# Modbus.net
KiCad netlist of a schematic drawn in Altium Designer
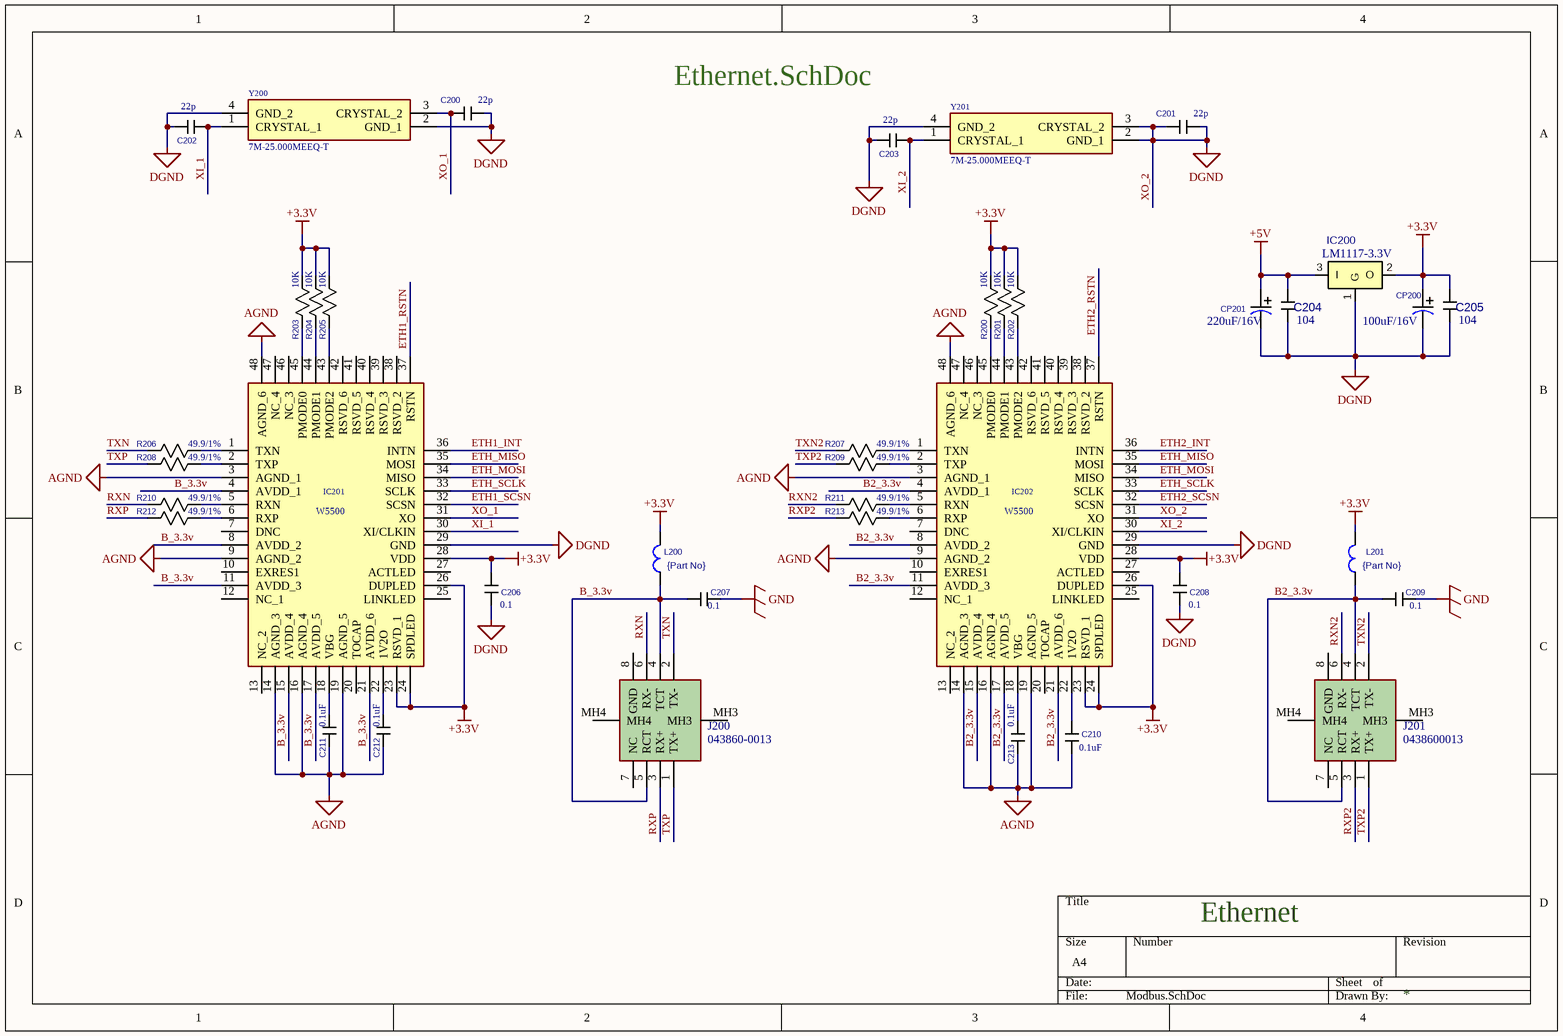
[diagram p0: Modbus.SchDoc]

(export (version "E")
  (design (tool "Eeschema 10.0.6"))
  (components
    (comp (ref "C200")
      (value "CS1608")
      (footprint "CC1608")
      (fields (field (name "PART NO.") "{Part No}") (field (name "규격") "22p"))
      (libsource (lib "KipoAlt") (part "CS1608"))
    )
    (comp (ref "C201")
      (value "CS1608")
      (footprint "CC1608")
      (fields (field (name "PART NO.") "{Part No}") (field (name "규격") "22p"))
      (libsource (lib "KipoAlt") (part "CS1608"))
    )
    (comp (ref "C202")
      (value "CS1608")
      (footprint "CC1608")
      (fields (field (name "PART NO.") "{Part No}") (field (name "규격") "22p"))
      (libsource (lib "KipoAlt") (part "CS1608"))
    )
    (comp (ref "C203")
      (value "CS1608")
      (footprint "CC1608")
      (fields (field (name "PART NO.") "{Part No}") (field (name "규격") "22p"))
      (libsource (lib "KipoAlt") (part "CS1608"))
    )
    (comp (ref "C204")
      (value "CS1608")
      (footprint "CC1608")
      (fields (field (name "PART NO.") "{Part No}") (field (name "규격") "104"))
      (libsource (lib "KipoAlt") (part "CS1608"))
    )
    (comp (ref "C205")
      (value "CS1608")
      (footprint "CC1608")
      (fields (field (name "PART NO.") "{Part No}") (field (name "규격") "104"))
      (libsource (lib "KipoAlt") (part "CS1608"))
    )
    (comp (ref "C206")
      (value "CS1608")
      (footprint "CC1608")
      (fields (field (name "PART NO.") "{Part No}") (field (name "규격") "0.1"))
      (libsource (lib "KipoAlt") (part "CS1608"))
    )
    (comp (ref "C207")
      (value "CS1608")
      (footprint "CC1608")
      (fields (field (name "PART NO.") "{Part No}") (field (name "규격") "0.1"))
      (libsource (lib "KipoAlt") (part "CS1608"))
    )
    (comp (ref "C208")
      (value "CS1608")
      (footprint "CC1608")
      (fields (field (name "PART NO.") "{Part No}") (field (name "규격") "0.1"))
      (libsource (lib "KipoAlt") (part "CS1608"))
    )
    (comp (ref "C209")
      (value "CS1608")
      (footprint "CC1608")
      (fields (field (name "PART NO.") "{Part No}") (field (name "규격") "0.1"))
      (libsource (lib "KipoAlt") (part "CS1608"))
    )
    (comp (ref "C210")
      (value "CS1608")
      (footprint "CC1608")
      (fields (field (name "PART NO.") "{Part No}") (field (name "규격") "0.1uF"))
      (libsource (lib "KipoAlt") (part "CS1608"))
    )
    (comp (ref "C211")
      (value "CS1608")
      (footprint "CC1608")
      (fields (field (name "PART NO.") "{Part No}") (field (name "규격") "0.1uF"))
      (libsource (lib "KipoAlt") (part "CS1608"))
    )
    (comp (ref "C212")
      (value "CS1608")
      (footprint "CC1608")
      (fields (field (name "PART NO.") "{Part No}") (field (name "규격") "0.1uF"))
      (libsource (lib "KipoAlt") (part "CS1608"))
    )
    (comp (ref "C213")
      (value "CS1608")
      (footprint "CC1608")
      (fields (field (name "PART NO.") "{Part No}") (field (name "규격") "0.1uF"))
      (libsource (lib "KipoAlt") (part "CS1608"))
    )
    (comp (ref "CP200")
      (value "CP5_SMT")
      (footprint "CP5_SMT")
      (fields (field (name "규격") "100uF/16V") (field (name "PART NO.") "{Part No}"))
      (libsource (lib "KipoAlt") (part "CP5_SMT"))
    )
    (comp (ref "CP201")
      (value "CP6_SMT")
      (footprint "CP6_SMT")
      (fields (field (name "PART NO.") "RV16V220 6.3X7.7 (ELNA / 삼영)") (field (name "규격") "220uF/16V"))
      (libsource (lib "KipoAlt") (part "CP6_SMT"))
    )
    (comp (ref "IC200")
      (value "1117SO")
      (footprint "SOT-223")
      (fields (field (name "PART NO.") "LM1117-3.3V"))
      (libsource (lib "KipoAlt") (part "1117SO"))
    )
    (comp (ref "IC201")
      (value "W5500")
      (footprint "KipoAlt:QFP50P900X900X160-48N")
      (description "Integrated Circuit")
      (libsource (lib "*") (part "W5500"))
    )
    (comp (ref "IC202")
      (value "W5500")
      (footprint "KipoAlt:QFP50P900X900X160-48N")
      (description "Integrated Circuit")
      (libsource (lib "*") (part "W5500"))
    )
    (comp (ref "J200")
      (value "043860-0013")
      (footprint "KipoAlt:0438600013")
      (description "Connector")
      (fields (field (name "MANUFACTURER_PART_NUMBER") "0438600013"))
      (libsource (lib "KipoAlt") (part "0438600013"))
    )
    (comp (ref "J201")
      (value "0438600013")
      (footprint "KipoAlt:0438600013")
      (description "Connector")
      (libsource (lib "KipoAlt") (part "0438600013"))
    )
    (comp (ref "L200")
      (value "L")
      (footprint "BEADC2012X110N")
      (fields (field (name "PART NO.") "{Part No}"))
      (libsource (lib "KipoAlt") (part "BEAD2012"))
    )
    (comp (ref "L201")
      (value "L")
      (footprint "BEADC2012X110N")
      (fields (field (name "PART NO.") "{Part No}"))
      (libsource (lib "KipoAlt") (part "BEAD2012"))
    )
    (comp (ref "R200")
      (value "R1608")
      (footprint "R1608N")
      (fields (field (name "규격") "10K") (field (name "PART NO.") "{Part No}"))
      (libsource (lib "KipoAlt") (part "R1608"))
    )
    (comp (ref "R201")
      (value "R1608")
      (footprint "R1608N")
      (fields (field (name "규격") "10K") (field (name "PART NO.") "{Part No}"))
      (libsource (lib "KipoAlt") (part "R1608"))
    )
    (comp (ref "R202")
      (value "R1608")
      (footprint "R1608N")
      (fields (field (name "규격") "10K") (field (name "PART NO.") "{Part No}"))
      (libsource (lib "KipoAlt") (part "R1608"))
    )
    (comp (ref "R203")
      (value "R1608")
      (footprint "R1608N")
      (fields (field (name "규격") "10K") (field (name "PART NO.") "{Part No}"))
      (libsource (lib "KipoAlt") (part "R1608"))
    )
    (comp (ref "R204")
      (value "R1608")
      (footprint "R1608N")
      (fields (field (name "규격") "10K") (field (name "PART NO.") "{Part No}"))
      (libsource (lib "KipoAlt") (part "R1608"))
    )
    (comp (ref "R205")
      (value "R1608")
      (footprint "R1608N")
      (fields (field (name "규격") "10K") (field (name "PART NO.") "{Part No}"))
      (libsource (lib "KipoAlt") (part "R1608"))
    )
    (comp (ref "R206")
      (value "R1608")
      (footprint "R1608N")
      (fields (field (name "규격") "49.9/1%") (field (name "PART NO.") "{Part No}"))
      (libsource (lib "KipoAlt") (part "R1608"))
    )
    (comp (ref "R207")
      (value "R1608")
      (footprint "R1608N")
      (fields (field (name "규격") "49.9/1%") (field (name "PART NO.") "{Part No}"))
      (libsource (lib "KipoAlt") (part "R1608"))
    )
    (comp (ref "R208")
      (value "R1608")
      (footprint "R1608N")
      (fields (field (name "규격") "49.9/1%") (field (name "PART NO.") "{Part No}"))
      (libsource (lib "KipoAlt") (part "R1608"))
    )
    (comp (ref "R209")
      (value "R1608")
      (footprint "R1608N")
      (fields (field (name "규격") "49.9/1%") (field (name "PART NO.") "{Part No}"))
      (libsource (lib "KipoAlt") (part "R1608"))
    )
    (comp (ref "R210")
      (value "R1608")
      (footprint "R1608N")
      (fields (field (name "규격") "49.9/1%") (field (name "PART NO.") "{Part No}"))
      (libsource (lib "KipoAlt") (part "R1608"))
    )
    (comp (ref "R211")
      (value "R1608")
      (footprint "R1608N")
      (fields (field (name "규격") "49.9/1%") (field (name "PART NO.") "{Part No}"))
      (libsource (lib "KipoAlt") (part "R1608"))
    )
    (comp (ref "R212")
      (value "R1608")
      (footprint "R1608N")
      (fields (field (name "규격") "49.9/1%") (field (name "PART NO.") "{Part No}"))
      (libsource (lib "KipoAlt") (part "R1608"))
    )
    (comp (ref "R213")
      (value "R1608")
      (footprint "R1608N")
      (fields (field (name "규격") "49.9/1%") (field (name "PART NO.") "{Part No}"))
      (libsource (lib "KipoAlt") (part "R1608"))
    )
    (comp (ref "Y200")
      (value "7M-25.000MEEQ-T")
      (footprint "KipoAlt:7M25000MEEQT")
      (description "Crystal or Oscillator")
      (fields (field (name "MOUSER PART NUMBER") "717-7M-25.000MEEQ-T"))
      (libsource (lib "*") (part "7M-25.000MEEQ-T"))
    )
    (comp (ref "Y201")
      (value "7M-25.000MEEQ-T")
      (footprint "KipoAlt:7M25000MEEQT")
      (description "Crystal or Oscillator")
      (fields (field (name "MOUSER PART NUMBER") "717-7M-25.000MEEQ-T"))
      (libsource (lib "*") (part "7M-25.000MEEQ-T"))
    )
  )
  (nets
    (net (code "1") (name "+3.3V") (class "Default")
      (node (ref "C205") (pin "2") (pintype "passive"))
      (node (ref "C206") (pin "2") (pintype "passive"))
      (node (ref "C208") (pin "2") (pintype "passive"))
      (node (ref "CP200") (pin "2") (pintype "passive"))
      (node (ref "IC200") (pin "2") (pinfunction "O_2") (pintype "passive"))
      (node (ref "IC201") (pin "23") (pinfunction "RSVD_1_23") (pintype "passive"))
      (node (ref "IC201") (pin "24") (pinfunction "SPDLED_24") (pintype "passive"))
      (node (ref "IC201") (pin "26") (pinfunction "DUPLED_26") (pintype "passive"))
      (node (ref "IC201") (pin "28") (pinfunction "VDD_28") (pintype "passive"))
      (node (ref "IC202") (pin "23") (pinfunction "RSVD_1_23") (pintype "passive"))
      (node (ref "IC202") (pin "24") (pinfunction "SPDLED_24") (pintype "passive"))
      (node (ref "IC202") (pin "26") (pinfunction "DUPLED_26") (pintype "passive"))
      (node (ref "IC202") (pin "28") (pinfunction "VDD_28") (pintype "passive"))
      (node (ref "L200") (pin "1") (pintype "passive"))
      (node (ref "L201") (pin "1") (pintype "passive"))
      (node (ref "R200") (pin "1") (pintype "passive"))
      (node (ref "R201") (pin "1") (pintype "passive"))
      (node (ref "R202") (pin "1") (pintype "passive"))
      (node (ref "R203") (pin "1") (pintype "passive"))
      (node (ref "R204") (pin "1") (pintype "passive"))
      (node (ref "R205") (pin "1") (pintype "passive"))
    )
    (net (code "2") (name "+5V") (class "Default")
      (node (ref "C204") (pin "2") (pintype "passive"))
      (node (ref "CP201") (pin "2") (pintype "passive"))
      (node (ref "IC200") (pin "3") (pinfunction "I_3") (pintype "passive"))
    )
    (net (code "3") (name "/B2_3.3v") (class "Default")
      (node (ref "C209") (pin "2") (pintype "passive"))
      (node (ref "IC202") (pin "11") (pinfunction "AVDD_3_11") (pintype "passive"))
      (node (ref "IC202") (pin "15") (pinfunction "AVDD_4_15") (pintype "passive"))
      (node (ref "IC202") (pin "17") (pinfunction "AVDD_5_17") (pintype "passive"))
      (node (ref "IC202") (pin "21") (pinfunction "AVDD_6_21") (pintype "passive"))
      (node (ref "IC202") (pin "4") (pinfunction "AVDD_1_4") (pintype "passive"))
      (node (ref "IC202") (pin "8") (pinfunction "AVDD_2_8") (pintype "passive"))
      (node (ref "J201") (pin "4") (pinfunction "TCT_4") (pintype "passive"))
      (node (ref "J201") (pin "5") (pinfunction "RCT_5") (pintype "passive"))
      (node (ref "L201") (pin "2") (pintype "passive"))
    )
    (net (code "4") (name "/B_3.3v") (class "Default")
      (node (ref "C207") (pin "2") (pintype "passive"))
      (node (ref "IC201") (pin "11") (pinfunction "AVDD_3_11") (pintype "passive"))
      (node (ref "IC201") (pin "15") (pinfunction "AVDD_4_15") (pintype "passive"))
      (node (ref "IC201") (pin "17") (pinfunction "AVDD_5_17") (pintype "passive"))
      (node (ref "IC201") (pin "21") (pinfunction "AVDD_6_21") (pintype "passive"))
      (node (ref "IC201") (pin "4") (pinfunction "AVDD_1_4") (pintype "passive"))
      (node (ref "IC201") (pin "8") (pinfunction "AVDD_2_8") (pintype "passive"))
      (node (ref "J200") (pin "4") (pinfunction "TCT_4") (pintype "passive"))
      (node (ref "J200") (pin "5") (pinfunction "RCT_5") (pintype "passive"))
      (node (ref "L200") (pin "2") (pintype "passive"))
    )
    (net (code "5") (name "/ETH1_INT") (class "Default")
      (node (ref "IC201") (pin "36") (pinfunction "INTN_36") (pintype "passive"))
    )
    (net (code "6") (name "/ETH1_RSTN") (class "Default")
      (node (ref "IC201") (pin "37") (pinfunction "RSTN_37") (pintype "passive"))
    )
    (net (code "7") (name "/ETH1_SCSN") (class "Default")
      (node (ref "IC201") (pin "32") (pinfunction "SCSN_32") (pintype "passive"))
    )
    (net (code "8") (name "/ETH2_INT") (class "Default")
      (node (ref "IC202") (pin "36") (pinfunction "INTN_36") (pintype "passive"))
    )
    (net (code "9") (name "/ETH2_RSTN") (class "Default")
      (node (ref "IC202") (pin "37") (pinfunction "RSTN_37") (pintype "passive"))
    )
    (net (code "10") (name "/ETH2_SCSN") (class "Default")
      (node (ref "IC202") (pin "32") (pinfunction "SCSN_32") (pintype "passive"))
    )
    (net (code "11") (name "/ETH_MISO") (class "Default")
      (node (ref "IC201") (pin "35") (pinfunction "MOSI_35") (pintype "passive"))
      (node (ref "IC202") (pin "35") (pinfunction "MOSI_35") (pintype "passive"))
    )
    (net (code "12") (name "/ETH_MOSI") (class "Default")
      (node (ref "IC201") (pin "34") (pinfunction "MISO_34") (pintype "passive"))
      (node (ref "IC202") (pin "34") (pinfunction "MISO_34") (pintype "passive"))
    )
    (net (code "13") (name "/ETH_SCLK") (class "Default")
      (node (ref "IC201") (pin "33") (pinfunction "SCLK_33") (pintype "passive"))
      (node (ref "IC202") (pin "33") (pinfunction "SCLK_33") (pintype "passive"))
    )
    (net (code "14") (name "/RXN") (class "Default")
      (node (ref "J200") (pin "6") (pinfunction "RX-_6") (pintype "passive"))
      (node (ref "R210") (pin "1") (pintype "passive"))
    )
    (net (code "15") (name "/RXN2") (class "Default")
      (node (ref "J201") (pin "6") (pinfunction "RX-_6") (pintype "passive"))
      (node (ref "R211") (pin "1") (pintype "passive"))
    )
    (net (code "16") (name "/RXP") (class "Default")
      (node (ref "J200") (pin "3") (pinfunction "RX+_3") (pintype "passive"))
      (node (ref "R212") (pin "1") (pintype "passive"))
    )
    (net (code "17") (name "/RXP2") (class "Default")
      (node (ref "J201") (pin "3") (pinfunction "RX+_3") (pintype "passive"))
      (node (ref "R213") (pin "1") (pintype "passive"))
    )
    (net (code "18") (name "/TXN") (class "Default")
      (node (ref "J200") (pin "2") (pinfunction "TX-_2") (pintype "passive"))
      (node (ref "R206") (pin "1") (pintype "passive"))
    )
    (net (code "19") (name "/TXN2") (class "Default")
      (node (ref "J201") (pin "2") (pinfunction "TX-_2") (pintype "passive"))
      (node (ref "R207") (pin "1") (pintype "passive"))
    )
    (net (code "20") (name "/TXP") (class "Default")
      (node (ref "J200") (pin "1") (pinfunction "TX+_1") (pintype "passive"))
      (node (ref "R208") (pin "1") (pintype "passive"))
    )
    (net (code "21") (name "/TXP2") (class "Default")
      (node (ref "J201") (pin "1") (pinfunction "TX+_1") (pintype "passive"))
      (node (ref "R209") (pin "1") (pintype "passive"))
    )
    (net (code "22") (name "/XI_1") (class "Default")
      (node (ref "C202") (pin "1") (pintype "passive"))
      (node (ref "IC201") (pin "30") (pinfunction "XI/CLKIN_30") (pintype "passive"))
      (node (ref "Y200") (pin "1") (pinfunction "CRYSTAL_1_1") (pintype "passive"))
    )
    (net (code "23") (name "/XI_2") (class "Default")
      (node (ref "C203") (pin "1") (pintype "passive"))
      (node (ref "IC202") (pin "30") (pinfunction "XI/CLKIN_30") (pintype "passive"))
      (node (ref "Y201") (pin "1") (pinfunction "CRYSTAL_1_1") (pintype "passive"))
    )
    (net (code "24") (name "/XO_1") (class "Default")
      (node (ref "C200") (pin "2") (pintype "passive"))
      (node (ref "IC201") (pin "31") (pinfunction "XO_31") (pintype "passive"))
      (node (ref "Y200") (pin "3") (pinfunction "CRYSTAL_2_3") (pintype "passive"))
    )
    (net (code "25") (name "AGND") (class "Default")
      (node (ref "C210") (pin "2") (pintype "passive"))
      (node (ref "C211") (pin "2") (pintype "passive"))
      (node (ref "C212") (pin "2") (pintype "passive"))
      (node (ref "C213") (pin "2") (pintype "passive"))
      (node (ref "IC201") (pin "14") (pinfunction "AGND_3_14") (pintype "passive"))
      (node (ref "IC201") (pin "16") (pinfunction "AGND_4_16") (pintype "passive"))
      (node (ref "IC201") (pin "19") (pinfunction "AGND_5_19") (pintype "passive"))
      (node (ref "IC201") (pin "3") (pinfunction "AGND_1_3") (pintype "passive"))
      (node (ref "IC201") (pin "48") (pinfunction "AGND_6_48") (pintype "passive"))
      (node (ref "IC201") (pin "9") (pinfunction "AGND_2_9") (pintype "passive"))
      (node (ref "IC202") (pin "14") (pinfunction "AGND_3_14") (pintype "passive"))
      (node (ref "IC202") (pin "16") (pinfunction "AGND_4_16") (pintype "passive"))
      (node (ref "IC202") (pin "19") (pinfunction "AGND_5_19") (pintype "passive"))
      (node (ref "IC202") (pin "3") (pinfunction "AGND_1_3") (pintype "passive"))
      (node (ref "IC202") (pin "48") (pinfunction "AGND_6_48") (pintype "passive"))
      (node (ref "IC202") (pin "9") (pinfunction "AGND_2_9") (pintype "passive"))
    )
    (net (code "26") (name "DGND") (class "Default")
      (node (ref "C200") (pin "1") (pintype "passive"))
      (node (ref "C201") (pin "1") (pintype "passive"))
      (node (ref "C201") (pin "2") (pintype "passive"))
      (node (ref "C202") (pin "2") (pintype "passive"))
      (node (ref "C203") (pin "2") (pintype "passive"))
      (node (ref "C204") (pin "1") (pintype "passive"))
      (node (ref "C205") (pin "1") (pintype "passive"))
      (node (ref "C206") (pin "1") (pintype "passive"))
      (node (ref "C208") (pin "1") (pintype "passive"))
      (node (ref "CP200") (pin "1") (pintype "passive"))
      (node (ref "CP201") (pin "1") (pintype "passive"))
      (node (ref "IC200") (pin "1") (pinfunction "G_1") (pintype "passive"))
      (node (ref "IC201") (pin "29") (pinfunction "GND_29") (pintype "passive"))
      (node (ref "IC202") (pin "29") (pinfunction "GND_29") (pintype "passive"))
      (node (ref "IC202") (pin "31") (pinfunction "XO_31") (pintype "passive"))
      (node (ref "Y200") (pin "2") (pinfunction "GND_1_2") (pintype "passive"))
      (node (ref "Y200") (pin "4") (pinfunction "GND_2_4") (pintype "passive"))
      (node (ref "Y201") (pin "2") (pinfunction "GND_1_2") (pintype "passive"))
      (node (ref "Y201") (pin "3") (pinfunction "CRYSTAL_2_3") (pintype "passive"))
      (node (ref "Y201") (pin "4") (pinfunction "GND_2_4") (pintype "passive"))
    )
    (net (code "27") (name "GND") (class "Default")
      (node (ref "C207") (pin "1") (pintype "passive"))
      (node (ref "C209") (pin "1") (pintype "passive"))
    )
    (net (code "28") (name "Net-(IC201-1V2O)") (class "Default")
      (node (ref "C212") (pin "1") (pintype "passive"))
      (node (ref "IC201") (pin "22") (pinfunction "1V2O_22") (pintype "passive"))
    )
    (net (code "29") (name "Net-(IC201-PMODE0)") (class "Default")
      (node (ref "IC201") (pin "45") (pinfunction "PMODE0_45") (pintype "passive"))
      (node (ref "R203") (pin "2") (pintype "passive"))
    )
    (net (code "30") (name "Net-(IC201-PMODE1)") (class "Default")
      (node (ref "IC201") (pin "44") (pinfunction "PMODE1_44") (pintype "passive"))
      (node (ref "R204") (pin "2") (pintype "passive"))
    )
    (net (code "31") (name "Net-(IC201-PMODE2)") (class "Default")
      (node (ref "IC201") (pin "43") (pinfunction "PMODE2_43") (pintype "passive"))
      (node (ref "R205") (pin "2") (pintype "passive"))
    )
    (net (code "32") (name "Net-(IC201-RXN)") (class "Default")
      (node (ref "IC201") (pin "5") (pinfunction "RXN_5") (pintype "passive"))
      (node (ref "R210") (pin "2") (pintype "passive"))
    )
    (net (code "33") (name "Net-(IC201-RXP)") (class "Default")
      (node (ref "IC201") (pin "6") (pinfunction "RXP_6") (pintype "passive"))
      (node (ref "R212") (pin "2") (pintype "passive"))
    )
    (net (code "34") (name "Net-(IC201-TXN)") (class "Default")
      (node (ref "IC201") (pin "1") (pinfunction "TXN_1") (pintype "passive"))
      (node (ref "R206") (pin "2") (pintype "passive"))
    )
    (net (code "35") (name "Net-(IC201-TXP)") (class "Default")
      (node (ref "IC201") (pin "2") (pinfunction "TXP_2") (pintype "passive"))
      (node (ref "R208") (pin "2") (pintype "passive"))
    )
    (net (code "36") (name "Net-(IC201-VBG)") (class "Default")
      (node (ref "C211") (pin "1") (pintype "passive"))
      (node (ref "IC201") (pin "18") (pinfunction "VBG_18") (pintype "passive"))
    )
    (net (code "37") (name "Net-(IC202-1V2O)") (class "Default")
      (node (ref "C210") (pin "1") (pintype "passive"))
      (node (ref "IC202") (pin "22") (pinfunction "1V2O_22") (pintype "passive"))
    )
    (net (code "38") (name "Net-(IC202-PMODE0)") (class "Default")
      (node (ref "IC202") (pin "45") (pinfunction "PMODE0_45") (pintype "passive"))
      (node (ref "R200") (pin "2") (pintype "passive"))
    )
    (net (code "39") (name "Net-(IC202-PMODE1)") (class "Default")
      (node (ref "IC202") (pin "44") (pinfunction "PMODE1_44") (pintype "passive"))
      (node (ref "R201") (pin "2") (pintype "passive"))
    )
    (net (code "40") (name "Net-(IC202-PMODE2)") (class "Default")
      (node (ref "IC202") (pin "43") (pinfunction "PMODE2_43") (pintype "passive"))
      (node (ref "R202") (pin "2") (pintype "passive"))
    )
    (net (code "41") (name "Net-(IC202-RXN)") (class "Default")
      (node (ref "IC202") (pin "5") (pinfunction "RXN_5") (pintype "passive"))
      (node (ref "R211") (pin "2") (pintype "passive"))
    )
    (net (code "42") (name "Net-(IC202-RXP)") (class "Default")
      (node (ref "IC202") (pin "6") (pinfunction "RXP_6") (pintype "passive"))
      (node (ref "R213") (pin "2") (pintype "passive"))
    )
    (net (code "43") (name "Net-(IC202-TXN)") (class "Default")
      (node (ref "IC202") (pin "1") (pinfunction "TXN_1") (pintype "passive"))
      (node (ref "R207") (pin "2") (pintype "passive"))
    )
    (net (code "44") (name "Net-(IC202-TXP)") (class "Default")
      (node (ref "IC202") (pin "2") (pinfunction "TXP_2") (pintype "passive"))
      (node (ref "R209") (pin "2") (pintype "passive"))
    )
    (net (code "45") (name "Net-(IC202-VBG)") (class "Default")
      (node (ref "C213") (pin "1") (pintype "passive"))
      (node (ref "IC202") (pin "18") (pinfunction "VBG_18") (pintype "passive"))
    )
    (net (code "46") (name "unconnected-(IC200-Pad4)") (class "Default")
      (node (ref "IC200") (pin "4") (pintype "passive"))
    )
    (net (code "47") (name "unconnected-(IC201-ACTLED-Pad27)") (class "Default")
      (node (ref "IC201") (pin "27") (pinfunction "ACTLED_27") (pintype "passive"))
    )
    (net (code "48") (name "unconnected-(IC201-DNC-Pad7)") (class "Default")
      (node (ref "IC201") (pin "7") (pinfunction "DNC_7") (pintype "passive"))
    )
    (net (code "49") (name "unconnected-(IC201-EXRES1-Pad10)") (class "Default")
      (node (ref "IC201") (pin "10") (pinfunction "EXRES1_10") (pintype "passive"))
    )
    (net (code "50") (name "unconnected-(IC201-LINKLED-Pad25)") (class "Default")
      (node (ref "IC201") (pin "25") (pinfunction "LINKLED_25") (pintype "passive"))
    )
    (net (code "51") (name "unconnected-(IC201-NC_1-Pad12)") (class "Default")
      (node (ref "IC201") (pin "12") (pinfunction "NC_1_12") (pintype "passive"))
    )
    (net (code "52") (name "unconnected-(IC201-NC_2-Pad13)") (class "Default")
      (node (ref "IC201") (pin "13") (pinfunction "NC_2_13") (pintype "passive"))
    )
    (net (code "53") (name "unconnected-(IC201-NC_3-Pad46)") (class "Default")
      (node (ref "IC201") (pin "46") (pinfunction "NC_3_46") (pintype "passive"))
    )
    (net (code "54") (name "unconnected-(IC201-NC_4-Pad47)") (class "Default")
      (node (ref "IC201") (pin "47") (pinfunction "NC_4_47") (pintype "passive"))
    )
    (net (code "55") (name "unconnected-(IC201-RSVD_2-Pad38)") (class "Default")
      (node (ref "IC201") (pin "38") (pinfunction "RSVD_2_38") (pintype "passive"))
    )
    (net (code "56") (name "unconnected-(IC201-RSVD_3-Pad39)") (class "Default")
      (node (ref "IC201") (pin "39") (pinfunction "RSVD_3_39") (pintype "passive"))
    )
    (net (code "57") (name "unconnected-(IC201-RSVD_4-Pad40)") (class "Default")
      (node (ref "IC201") (pin "40") (pinfunction "RSVD_4_40") (pintype "passive"))
    )
    (net (code "58") (name "unconnected-(IC201-RSVD_5-Pad41)") (class "Default")
      (node (ref "IC201") (pin "41") (pinfunction "RSVD_5_41") (pintype "passive"))
    )
    (net (code "59") (name "unconnected-(IC201-RSVD_6-Pad42)") (class "Default")
      (node (ref "IC201") (pin "42") (pinfunction "RSVD_6_42") (pintype "passive"))
    )
    (net (code "60") (name "unconnected-(IC201-TOCAP-Pad20)") (class "Default")
      (node (ref "IC201") (pin "20") (pinfunction "TOCAP_20") (pintype "passive"))
    )
    (net (code "61") (name "unconnected-(IC202-ACTLED-Pad27)") (class "Default")
      (node (ref "IC202") (pin "27") (pinfunction "ACTLED_27") (pintype "passive"))
    )
    (net (code "62") (name "unconnected-(IC202-DNC-Pad7)") (class "Default")
      (node (ref "IC202") (pin "7") (pinfunction "DNC_7") (pintype "passive"))
    )
    (net (code "63") (name "unconnected-(IC202-EXRES1-Pad10)") (class "Default")
      (node (ref "IC202") (pin "10") (pinfunction "EXRES1_10") (pintype "passive"))
    )
    (net (code "64") (name "unconnected-(IC202-LINKLED-Pad25)") (class "Default")
      (node (ref "IC202") (pin "25") (pinfunction "LINKLED_25") (pintype "passive"))
    )
    (net (code "65") (name "unconnected-(IC202-NC_1-Pad12)") (class "Default")
      (node (ref "IC202") (pin "12") (pinfunction "NC_1_12") (pintype "passive"))
    )
    (net (code "66") (name "unconnected-(IC202-NC_2-Pad13)") (class "Default")
      (node (ref "IC202") (pin "13") (pinfunction "NC_2_13") (pintype "passive"))
    )
    (net (code "67") (name "unconnected-(IC202-NC_3-Pad46)") (class "Default")
      (node (ref "IC202") (pin "46") (pinfunction "NC_3_46") (pintype "passive"))
    )
    (net (code "68") (name "unconnected-(IC202-NC_4-Pad47)") (class "Default")
      (node (ref "IC202") (pin "47") (pinfunction "NC_4_47") (pintype "passive"))
    )
    (net (code "69") (name "unconnected-(IC202-RSVD_2-Pad38)") (class "Default")
      (node (ref "IC202") (pin "38") (pinfunction "RSVD_2_38") (pintype "passive"))
    )
    (net (code "70") (name "unconnected-(IC202-RSVD_3-Pad39)") (class "Default")
      (node (ref "IC202") (pin "39") (pinfunction "RSVD_3_39") (pintype "passive"))
    )
    (net (code "71") (name "unconnected-(IC202-RSVD_4-Pad40)") (class "Default")
      (node (ref "IC202") (pin "40") (pinfunction "RSVD_4_40") (pintype "passive"))
    )
    (net (code "72") (name "unconnected-(IC202-RSVD_5-Pad41)") (class "Default")
      (node (ref "IC202") (pin "41") (pinfunction "RSVD_5_41") (pintype "passive"))
    )
    (net (code "73") (name "unconnected-(IC202-RSVD_6-Pad42)") (class "Default")
      (node (ref "IC202") (pin "42") (pinfunction "RSVD_6_42") (pintype "passive"))
    )
    (net (code "74") (name "unconnected-(IC202-TOCAP-Pad20)") (class "Default")
      (node (ref "IC202") (pin "20") (pinfunction "TOCAP_20") (pintype "passive"))
    )
    (net (code "75") (name "unconnected-(J200-GND-Pad8)") (class "Default")
      (node (ref "J200") (pin "8") (pinfunction "GND_8") (pintype "passive"))
    )
    (net (code "76") (name "unconnected-(J200-NC-Pad7)") (class "Default")
      (node (ref "J200") (pin "7") (pinfunction "NC_7") (pintype "passive"))
    )
    (net (code "77") (name "unconnected-(J200-PadMH3)") (class "Default")
      (node (ref "J200") (pin "MH3") (pinfunction "MH3_MH3") (pintype "passive"))
    )
    (net (code "78") (name "unconnected-(J200-PadMH4)") (class "Default")
      (node (ref "J200") (pin "MH4") (pinfunction "MH4_MH4") (pintype "passive"))
    )
    (net (code "79") (name "unconnected-(J201-GND-Pad8)") (class "Default")
      (node (ref "J201") (pin "8") (pinfunction "GND_8") (pintype "passive"))
    )
    (net (code "80") (name "unconnected-(J201-NC-Pad7)") (class "Default")
      (node (ref "J201") (pin "7") (pinfunction "NC_7") (pintype "passive"))
    )
    (net (code "81") (name "unconnected-(J201-PadMH3)") (class "Default")
      (node (ref "J201") (pin "MH3") (pinfunction "MH3_MH3") (pintype "passive"))
    )
    (net (code "82") (name "unconnected-(J201-PadMH4)") (class "Default")
      (node (ref "J201") (pin "MH4") (pinfunction "MH4_MH4") (pintype "passive"))
    )
  )
)
